# v1.net
KiCad netlist of a schematic drawn in EAGLE
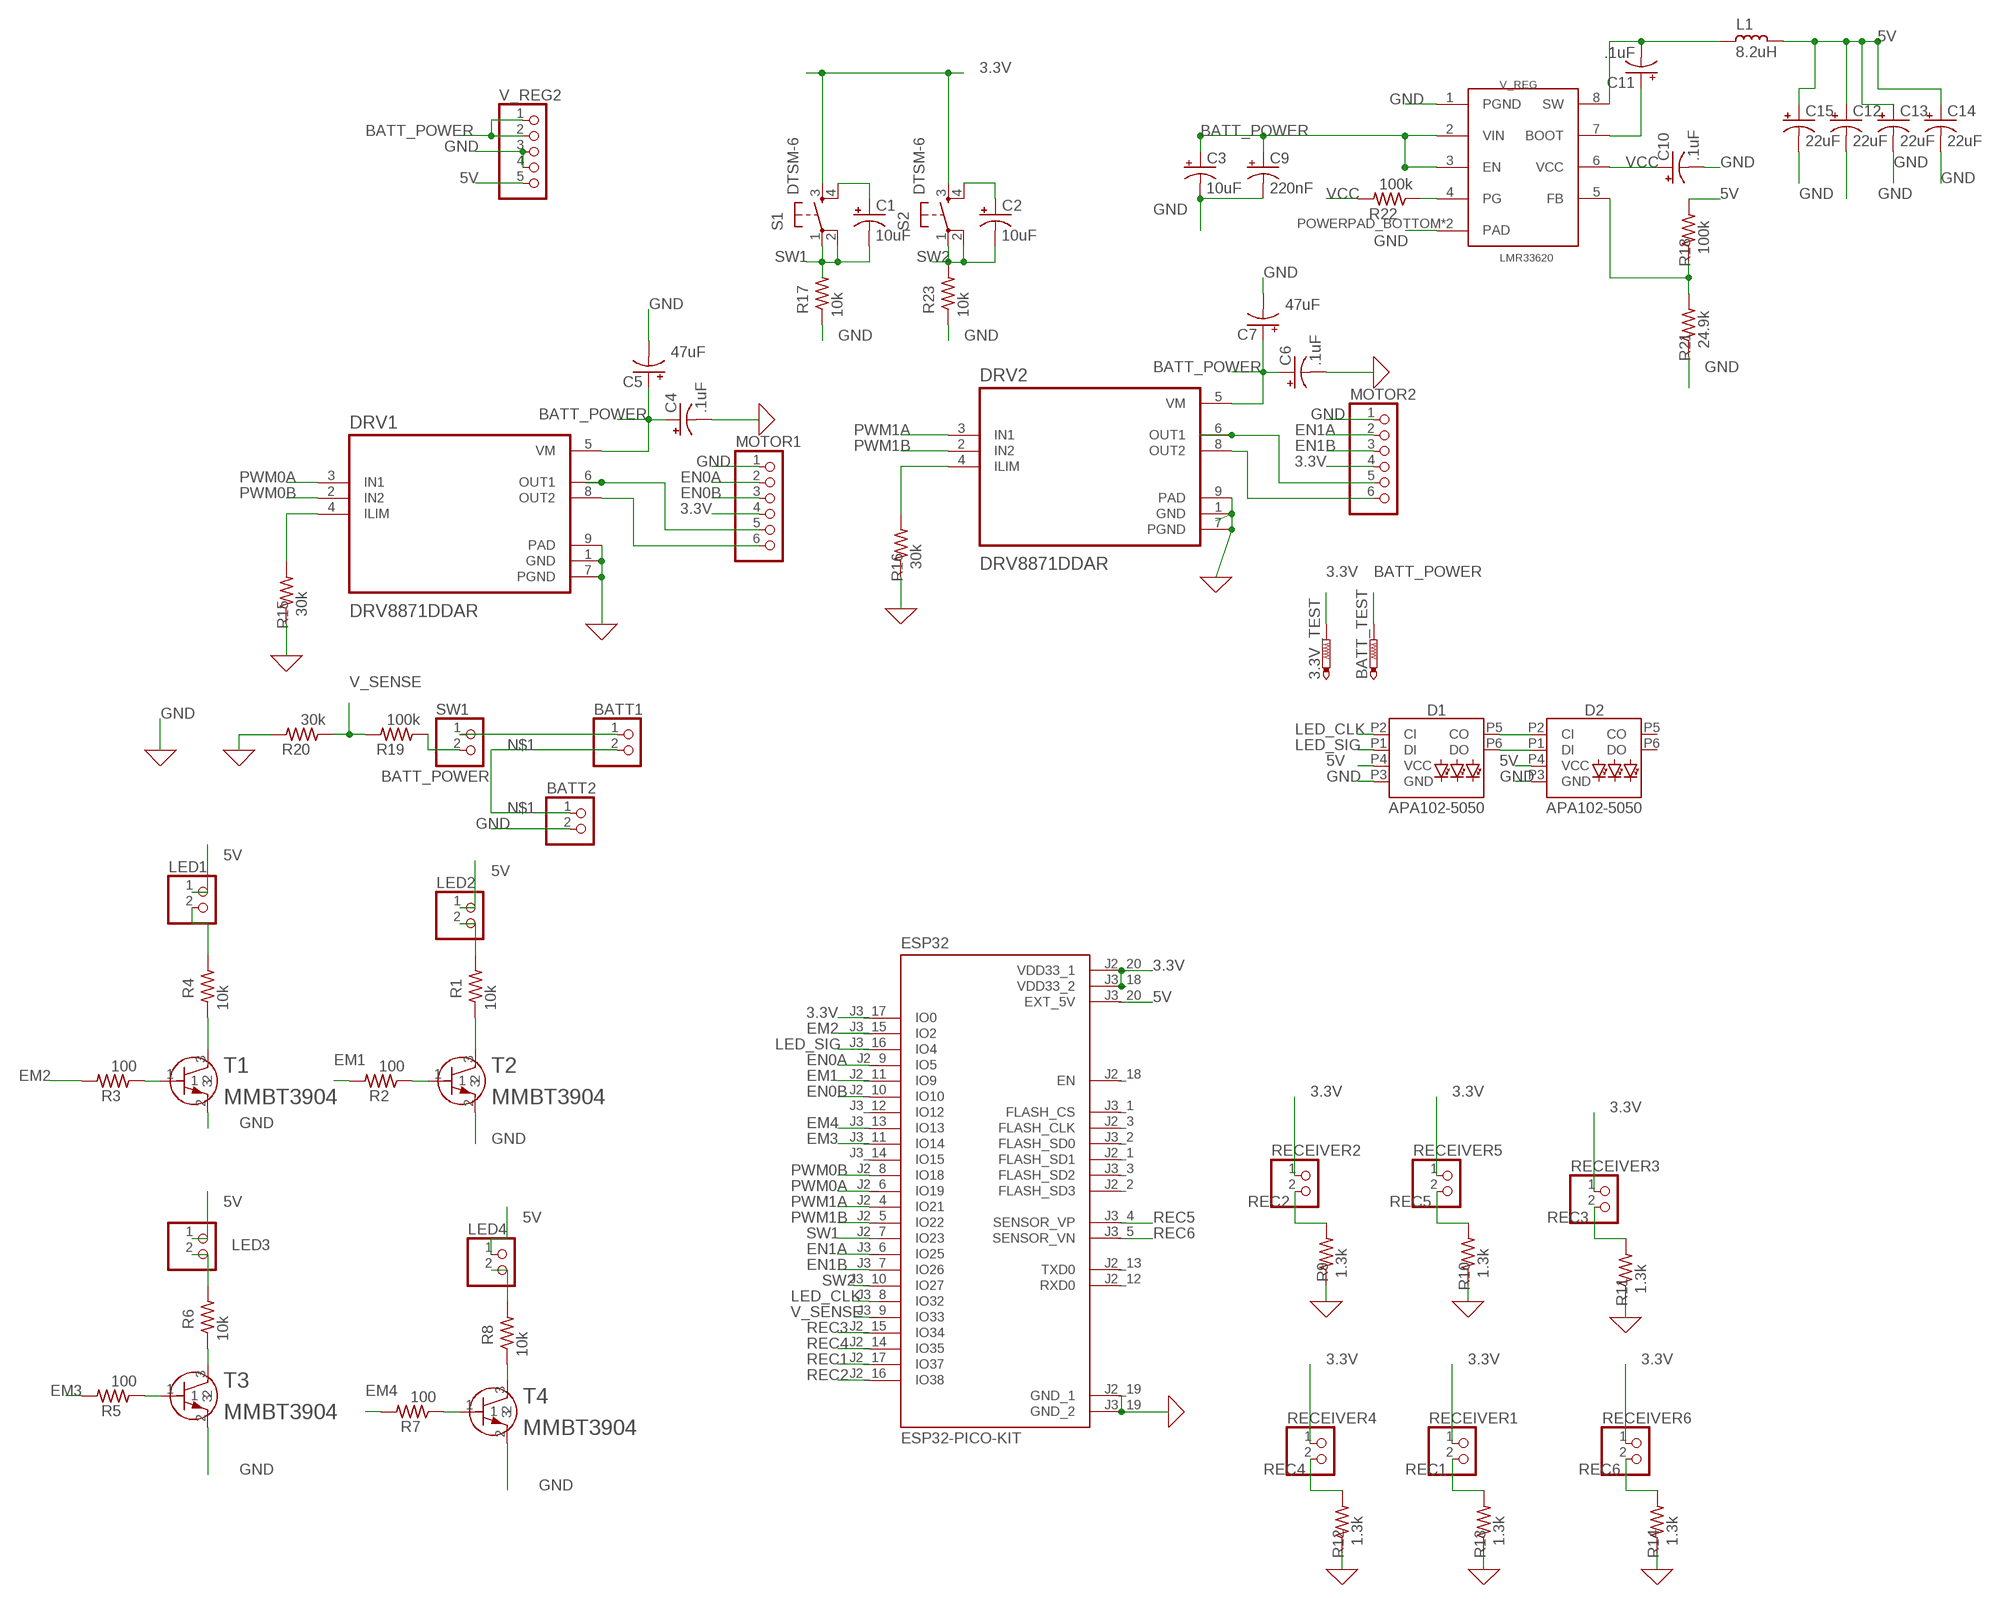
[diagram p0: schematic, sheet 1]

(export (version "E")
  (design (tool "Eeschema 10.0.6"))
  (components
    (comp (ref "3.3V_TEST")
      (value "PTR1B1,27")
      (footprint "eagle-import:B1,27")
      (libsource (lib "eagle-import") (part "PTR1B1,27"))
    )
    (comp (ref "BATT1")
      (value "PINHD-1X2")
      (footprint "eagle-import:1X02")
      (libsource (lib "eagle-import") (part "PINHD-1X2"))
    )
    (comp (ref "BATT2")
      (value "PINHD-1X2")
      (footprint "eagle-import:1X02")
      (libsource (lib "eagle-import") (part "PINHD-1X2"))
    )
    (comp (ref "BATT_TEST")
      (value "PTR1B1,27")
      (footprint "eagle-import:B1,27")
      (libsource (lib "eagle-import") (part "PTR1B1,27"))
    )
    (comp (ref "C1")
      (value "10uF")
      (footprint "eagle-import:A_3216-18R")
      (libsource (lib "eagle-import") (part "CPOL-USA/3216-18R"))
    )
    (comp (ref "C2")
      (value "10uF")
      (footprint "eagle-import:A_3216-18R")
      (libsource (lib "eagle-import") (part "CPOL-USA/3216-18R"))
    )
    (comp (ref "C3")
      (value "10uF")
      (footprint "eagle-import:A_3216-18R")
      (libsource (lib "eagle-import") (part "CPOL-USA/3216-18R"))
    )
    (comp (ref "C4")
      (value ".1uF")
      (footprint "eagle-import:A_3216-18R")
      (libsource (lib "eagle-import") (part "CPOL-USA/3216-18R"))
    )
    (comp (ref "C5")
      (value "47uF")
      (footprint "eagle-import:150CLZ-0810")
      (libsource (lib "eagle-import") (part "CPOL-US150CLZ-0810"))
    )
    (comp (ref "C6")
      (value ".1uF")
      (footprint "eagle-import:A_3216-18R")
      (libsource (lib "eagle-import") (part "CPOL-USA/3216-18R"))
    )
    (comp (ref "C7")
      (value "47uF")
      (footprint "eagle-import:150CLZ-0810")
      (libsource (lib "eagle-import") (part "CPOL-US150CLZ-0810"))
    )
    (comp (ref "C9")
      (value "220nF")
      (footprint "eagle-import:A_3216-18R")
      (libsource (lib "eagle-import") (part "CPOL-USA/3216-18R"))
    )
    (comp (ref "C10")
      (value ".1uF")
      (footprint "eagle-import:A_3216-18R")
      (libsource (lib "eagle-import") (part "CPOL-USA/3216-18R"))
    )
    (comp (ref "C11")
      (value ".1uF")
      (footprint "eagle-import:A_3216-18R")
      (libsource (lib "eagle-import") (part "CPOL-USA/3216-18R"))
    )
    (comp (ref "C12")
      (value "22uF")
      (footprint "eagle-import:A_3216-18R")
      (libsource (lib "eagle-import") (part "CPOL-USA/3216-18R"))
    )
    (comp (ref "C13")
      (value "22uF")
      (footprint "eagle-import:A_3216-18R")
      (libsource (lib "eagle-import") (part "CPOL-USA/3216-18R"))
    )
    (comp (ref "C14")
      (value "22uF")
      (footprint "eagle-import:A_3216-18R")
      (libsource (lib "eagle-import") (part "CPOL-USA/3216-18R"))
    )
    (comp (ref "C15")
      (value "22uF")
      (footprint "eagle-import:A_3216-18R")
      (libsource (lib "eagle-import") (part "CPOL-USA/3216-18R"))
    )
    (comp (ref "D1")
      (value "APA102-5050")
      (footprint "eagle-import:APA102-5050")
      (libsource (lib "eagle-import") (part "APA102-5050"))
    )
    (comp (ref "D2")
      (value "APA102-5050")
      (footprint "eagle-import:APA102-5050")
      (libsource (lib "eagle-import") (part "APA102-5050"))
    )
    (comp (ref "DRV1")
      (value "DRV8871DDAR")
      (footprint "eagle-import:SOIC127P600X170-8N")
      (fields (field (name "DIGI-KEY_PART_NUMBER") "296-43024-1-ND") (field (name "MF") "Texas Instruments"))
      (libsource (lib "eagle-import") (part "DRV8871DDAR"))
    )
    (comp (ref "DRV2")
      (value "DRV8871DDAR")
      (footprint "eagle-import:SOIC127P600X170-8N")
      (fields (field (name "DIGI-KEY_PART_NUMBER") "296-43024-1-ND") (field (name "MF") "Texas Instruments"))
      (libsource (lib "eagle-import") (part "DRV8871DDAR"))
    )
    (comp (ref "ESP32")
      (value "ESP32-PICO-KIT")
      (footprint "eagle-import:XCVR_ESP32-PICO-KIT")
      (fields (field (name "MF") "Espressif Systems"))
      (libsource (lib "eagle-import") (part "ESP32-PICO-KIT"))
    )
    (comp (ref "L1")
      (value "8.2uH")
      (footprint "eagle-import:PM1812")
      (libsource (lib "eagle-import") (part "L_PM1812"))
    )
    (comp (ref "LED1")
      (value "PINHD-1X2")
      (footprint "eagle-import:1X02")
      (libsource (lib "eagle-import") (part "PINHD-1X2"))
    )
    (comp (ref "LED2")
      (value "PINHD-1X2")
      (footprint "eagle-import:1X02")
      (libsource (lib "eagle-import") (part "PINHD-1X2"))
    )
    (comp (ref "LED3")
      (value "PINHD-1X2")
      (footprint "eagle-import:1X02")
      (libsource (lib "eagle-import") (part "PINHD-1X2"))
    )
    (comp (ref "LED4")
      (value "PINHD-1X2")
      (footprint "eagle-import:1X02")
      (libsource (lib "eagle-import") (part "PINHD-1X2"))
    )
    (comp (ref "MOTOR1")
      (value "PINHD-1X6")
      (footprint "eagle-import:1X06")
      (libsource (lib "eagle-import") (part "PINHD-1X6"))
    )
    (comp (ref "MOTOR2")
      (value "PINHD-1X6")
      (footprint "eagle-import:1X06")
      (libsource (lib "eagle-import") (part "PINHD-1X6"))
    )
    (comp (ref "R1")
      (value "10k")
      (footprint "eagle-import:M1206")
      (libsource (lib "eagle-import") (part "R-US_M1206"))
    )
    (comp (ref "R2")
      (value "100")
      (footprint "eagle-import:M1206")
      (libsource (lib "eagle-import") (part "R-US_M1206"))
    )
    (comp (ref "R3")
      (value "100")
      (footprint "eagle-import:M1206")
      (libsource (lib "eagle-import") (part "R-US_M1206"))
    )
    (comp (ref "R4")
      (value "10k")
      (footprint "eagle-import:M1206")
      (libsource (lib "eagle-import") (part "R-US_M1206"))
    )
    (comp (ref "R5")
      (value "100")
      (footprint "eagle-import:M1206")
      (libsource (lib "eagle-import") (part "R-US_M1206"))
    )
    (comp (ref "R6")
      (value "10k")
      (footprint "eagle-import:M1206")
      (libsource (lib "eagle-import") (part "R-US_M1206"))
    )
    (comp (ref "R7")
      (value "100")
      (footprint "eagle-import:M1206")
      (libsource (lib "eagle-import") (part "R-US_M1206"))
    )
    (comp (ref "R8")
      (value "10k")
      (footprint "eagle-import:M1206")
      (libsource (lib "eagle-import") (part "R-US_M1206"))
    )
    (comp (ref "R9")
      (value "1.3k")
      (footprint "eagle-import:M1206")
      (libsource (lib "eagle-import") (part "R-US_M1206"))
    )
    (comp (ref "R10")
      (value "1.3k")
      (footprint "eagle-import:M1206")
      (libsource (lib "eagle-import") (part "R-US_M1206"))
    )
    (comp (ref "R11")
      (value "1.3k")
      (footprint "eagle-import:M1206")
      (libsource (lib "eagle-import") (part "R-US_M1206"))
    )
    (comp (ref "R12")
      (value "1.3k")
      (footprint "eagle-import:M1206")
      (libsource (lib "eagle-import") (part "R-US_M1206"))
    )
    (comp (ref "R13")
      (value "1.3k")
      (footprint "eagle-import:M1206")
      (libsource (lib "eagle-import") (part "R-US_M1206"))
    )
    (comp (ref "R14")
      (value "1.3k")
      (footprint "eagle-import:M1206")
      (libsource (lib "eagle-import") (part "R-US_M1206"))
    )
    (comp (ref "R15")
      (value "30k")
      (footprint "eagle-import:M1206")
      (libsource (lib "eagle-import") (part "R-US_M1206"))
    )
    (comp (ref "R16")
      (value "30k")
      (footprint "eagle-import:M1206")
      (libsource (lib "eagle-import") (part "R-US_M1206"))
    )
    (comp (ref "R17")
      (value "10k")
      (footprint "eagle-import:M1206")
      (libsource (lib "eagle-import") (part "R-US_M1206"))
    )
    (comp (ref "R18")
      (value "100k")
      (footprint "eagle-import:M1206")
      (libsource (lib "eagle-import") (part "R-US_M1206"))
    )
    (comp (ref "R19")
      (value "100k")
      (footprint "eagle-import:M1206")
      (libsource (lib "eagle-import") (part "R-US_M1206"))
    )
    (comp (ref "R20")
      (value "30k")
      (footprint "eagle-import:M1206")
      (libsource (lib "eagle-import") (part "R-US_M1206"))
    )
    (comp (ref "R21")
      (value "24.9k")
      (footprint "eagle-import:M1206")
      (libsource (lib "eagle-import") (part "R-US_M1206"))
    )
    (comp (ref "R22")
      (value "100k")
      (footprint "eagle-import:M1206")
      (libsource (lib "eagle-import") (part "R-US_M1206"))
    )
    (comp (ref "R23")
      (value "10k")
      (footprint "eagle-import:M1206")
      (libsource (lib "eagle-import") (part "R-US_M1206"))
    )
    (comp (ref "RECEIVER1")
      (value "PINHD-1X2")
      (footprint "eagle-import:1X02")
      (libsource (lib "eagle-import") (part "PINHD-1X2"))
    )
    (comp (ref "RECEIVER2")
      (value "PINHD-1X2")
      (footprint "eagle-import:1X02")
      (libsource (lib "eagle-import") (part "PINHD-1X2"))
    )
    (comp (ref "RECEIVER3")
      (value "PINHD-1X2")
      (footprint "eagle-import:1X02")
      (libsource (lib "eagle-import") (part "PINHD-1X2"))
    )
    (comp (ref "RECEIVER4")
      (value "PINHD-1X2")
      (footprint "eagle-import:1X02")
      (libsource (lib "eagle-import") (part "PINHD-1X2"))
    )
    (comp (ref "RECEIVER5")
      (value "PINHD-1X2")
      (footprint "eagle-import:1X02")
      (libsource (lib "eagle-import") (part "PINHD-1X2"))
    )
    (comp (ref "RECEIVER6")
      (value "PINHD-1X2")
      (footprint "eagle-import:1X02")
      (libsource (lib "eagle-import") (part "PINHD-1X2"))
    )
    (comp (ref "S1")
      (value "DTSM-6")
      (footprint "eagle-import:DTSM-6")
      (libsource (lib "eagle-import") (part "DTSM-6"))
    )
    (comp (ref "S2")
      (value "DTSM-6")
      (footprint "eagle-import:DTSM-6")
      (libsource (lib "eagle-import") (part "DTSM-6"))
    )
    (comp (ref "SW1")
      (value "PINHD-1X2")
      (footprint "eagle-import:1X02")
      (libsource (lib "eagle-import") (part "PINHD-1X2"))
    )
    (comp (ref "T1")
      (value "MMBT3904")
      (footprint "eagle-import:SOT23")
      (libsource (lib "eagle-import") (part "MMBT3904"))
    )
    (comp (ref "T2")
      (value "MMBT3904")
      (footprint "eagle-import:SOT23")
      (libsource (lib "eagle-import") (part "MMBT3904"))
    )
    (comp (ref "T3")
      (value "MMBT3904")
      (footprint "eagle-import:SOT23")
      (libsource (lib "eagle-import") (part "MMBT3904"))
    )
    (comp (ref "T4")
      (value "MMBT3904")
      (footprint "eagle-import:SOT23")
      (libsource (lib "eagle-import") (part "MMBT3904"))
    )
    (comp (ref "V_REG")
      (value "LMR33620")
      (footprint "eagle-import:SO-8_POWERPAD")
      (libsource (lib "eagle-import") (part "LMR33620"))
    )
    (comp (ref "V_REG2")
      (value "PINHD-1X5")
      (footprint "eagle-import:1X05")
      (libsource (lib "eagle-import") (part "PINHD-1X5"))
    )
  )
  (nets
    (net (code "1") (name "/3.3V") (class "Default")
      (node (ref "3.3V_TEST") (pin "TP") (pinfunction "TP_TP") (pintype "input"))
      (node (ref "ESP32") (pin "J2_20") (pinfunction "VDD33_1_J2_20") (pintype "power_in"))
      (node (ref "ESP32") (pin "J3_17") (pinfunction "IO0_J3_17") (pintype "bidirectional"))
      (node (ref "ESP32") (pin "J3_18") (pinfunction "VDD33_2_J3_18") (pintype "power_in"))
      (node (ref "MOTOR1") (pin "4") (pinfunction "4_4") (pintype "passive"))
      (node (ref "MOTOR2") (pin "4") (pinfunction "4_4") (pintype "passive"))
      (node (ref "RECEIVER1") (pin "1") (pinfunction "1_1") (pintype "passive"))
      (node (ref "RECEIVER2") (pin "1") (pinfunction "1_1") (pintype "passive"))
      (node (ref "RECEIVER3") (pin "1") (pinfunction "1_1") (pintype "passive"))
      (node (ref "RECEIVER4") (pin "1") (pinfunction "1_1") (pintype "passive"))
      (node (ref "RECEIVER5") (pin "1") (pinfunction "1_1") (pintype "passive"))
      (node (ref "RECEIVER6") (pin "1") (pinfunction "1_1") (pintype "passive"))
      (node (ref "S1") (pin "3") (pinfunction "3_3") (pintype "passive"))
      (node (ref "S2") (pin "3") (pinfunction "3_3") (pintype "passive"))
    )
    (net (code "2") (name "/5V") (class "Default")
      (node (ref "C12") (pin "+") (pinfunction "+_+") (pintype "passive"))
      (node (ref "C13") (pin "+") (pinfunction "+_+") (pintype "passive"))
      (node (ref "C14") (pin "+") (pinfunction "+_+") (pintype "passive"))
      (node (ref "C15") (pin "+") (pinfunction "+_+") (pintype "passive"))
      (node (ref "D1") (pin "P4") (pinfunction "VCC_P4") (pintype "bidirectional"))
      (node (ref "D2") (pin "P4") (pinfunction "VCC_P4") (pintype "bidirectional"))
      (node (ref "ESP32") (pin "J3_20") (pinfunction "EXT_5V_J3_20") (pintype "power_in"))
      (node (ref "L1") (pin "1") (pinfunction "1_1") (pintype "passive"))
      (node (ref "LED1") (pin "1") (pinfunction "1_1") (pintype "passive"))
      (node (ref "LED2") (pin "1") (pinfunction "1_1") (pintype "passive"))
      (node (ref "LED3") (pin "1") (pinfunction "1_1") (pintype "passive"))
      (node (ref "LED4") (pin "1") (pinfunction "1_1") (pintype "passive"))
      (node (ref "R18") (pin "2") (pinfunction "2_2") (pintype "passive"))
      (node (ref "V_REG2") (pin "5") (pinfunction "5_5") (pintype "passive"))
    )
    (net (code "3") (name "/BATT_POWER") (class "Default")
      (node (ref "BATT_TEST") (pin "TP") (pinfunction "TP_TP") (pintype "input"))
      (node (ref "C3") (pin "+") (pinfunction "+_+") (pintype "passive"))
      (node (ref "C4") (pin "+") (pinfunction "+_+") (pintype "passive"))
      (node (ref "C5") (pin "+") (pinfunction "+_+") (pintype "passive"))
      (node (ref "C6") (pin "+") (pinfunction "+_+") (pintype "passive"))
      (node (ref "C7") (pin "+") (pinfunction "+_+") (pintype "passive"))
      (node (ref "C9") (pin "+") (pinfunction "+_+") (pintype "passive"))
      (node (ref "DRV1") (pin "5") (pinfunction "VM_5") (pintype "power_in"))
      (node (ref "DRV2") (pin "5") (pinfunction "VM_5") (pintype "power_in"))
      (node (ref "R19") (pin "1") (pinfunction "1_1") (pintype "passive"))
      (node (ref "SW1") (pin "2") (pinfunction "2_2") (pintype "passive"))
      (node (ref "V_REG") (pin "2") (pinfunction "VIN_2") (pintype "bidirectional"))
      (node (ref "V_REG") (pin "3") (pinfunction "EN_3") (pintype "bidirectional"))
      (node (ref "V_REG2") (pin "1") (pinfunction "1_1") (pintype "passive"))
      (node (ref "V_REG2") (pin "2") (pinfunction "2_2") (pintype "passive"))
    )
    (net (code "4") (name "/EM1") (class "Default")
      (node (ref "ESP32") (pin "J2_11") (pinfunction "IO9_J2_11") (pintype "bidirectional"))
      (node (ref "R2") (pin "2") (pinfunction "2_2") (pintype "passive"))
    )
    (net (code "5") (name "/EM2") (class "Default")
      (node (ref "ESP32") (pin "J3_15") (pinfunction "IO2_J3_15") (pintype "bidirectional"))
      (node (ref "R3") (pin "2") (pinfunction "2_2") (pintype "passive"))
    )
    (net (code "6") (name "/EM3") (class "Default")
      (node (ref "ESP32") (pin "J3_11") (pinfunction "IO14_J3_11") (pintype "bidirectional"))
      (node (ref "R5") (pin "2") (pinfunction "2_2") (pintype "passive"))
    )
    (net (code "7") (name "/EM4") (class "Default")
      (node (ref "ESP32") (pin "J3_13") (pinfunction "IO13_J3_13") (pintype "bidirectional"))
      (node (ref "R7") (pin "2") (pinfunction "2_2") (pintype "passive"))
    )
    (net (code "8") (name "/EN0A") (class "Default")
      (node (ref "ESP32") (pin "J2_9") (pinfunction "IO5_J2_9") (pintype "bidirectional"))
      (node (ref "MOTOR1") (pin "2") (pinfunction "2_2") (pintype "passive"))
    )
    (net (code "9") (name "/EN0B") (class "Default")
      (node (ref "ESP32") (pin "J2_10") (pinfunction "IO10_J2_10") (pintype "bidirectional"))
      (node (ref "MOTOR1") (pin "3") (pinfunction "3_3") (pintype "passive"))
    )
    (net (code "10") (name "/EN1A") (class "Default")
      (node (ref "ESP32") (pin "J3_6") (pinfunction "IO25_J3_6") (pintype "bidirectional"))
      (node (ref "MOTOR2") (pin "2") (pinfunction "2_2") (pintype "passive"))
    )
    (net (code "11") (name "/EN1B") (class "Default")
      (node (ref "ESP32") (pin "J3_7") (pinfunction "IO26_J3_7") (pintype "bidirectional"))
      (node (ref "MOTOR2") (pin "3") (pinfunction "3_3") (pintype "passive"))
    )
    (net (code "12") (name "/LED_CLK") (class "Default")
      (node (ref "D1") (pin "P2") (pinfunction "CI_P2") (pintype "bidirectional"))
      (node (ref "ESP32") (pin "J3_8") (pinfunction "IO32_J3_8") (pintype "bidirectional"))
    )
    (net (code "13") (name "/LED_SIG") (class "Default")
      (node (ref "D1") (pin "P1") (pinfunction "DI_P1") (pintype "bidirectional"))
      (node (ref "ESP32") (pin "J3_16") (pinfunction "IO4_J3_16") (pintype "bidirectional"))
    )
    (net (code "14") (name "/N$1") (class "Default")
      (node (ref "BATT1") (pin "2") (pinfunction "2_2") (pintype "passive"))
      (node (ref "BATT2") (pin "1") (pinfunction "1_1") (pintype "passive"))
    )
    (net (code "15") (name "/PWM0A") (class "Default")
      (node (ref "DRV1") (pin "3") (pinfunction "IN1_3") (pintype "input"))
      (node (ref "ESP32") (pin "J2_6") (pinfunction "IO19_J2_6") (pintype "bidirectional"))
    )
    (net (code "16") (name "/PWM0B") (class "Default")
      (node (ref "DRV1") (pin "2") (pinfunction "IN2_2") (pintype "input"))
      (node (ref "ESP32") (pin "J2_8") (pinfunction "IO18_J2_8") (pintype "bidirectional"))
    )
    (net (code "17") (name "/PWM1A") (class "Default")
      (node (ref "DRV2") (pin "3") (pinfunction "IN1_3") (pintype "input"))
      (node (ref "ESP32") (pin "J2_4") (pinfunction "IO21_J2_4") (pintype "bidirectional"))
    )
    (net (code "18") (name "/PWM1B") (class "Default")
      (node (ref "DRV2") (pin "2") (pinfunction "IN2_2") (pintype "input"))
      (node (ref "ESP32") (pin "J2_5") (pinfunction "IO22_J2_5") (pintype "bidirectional"))
    )
    (net (code "19") (name "/REC1") (class "Default")
      (node (ref "ESP32") (pin "J2_17") (pinfunction "IO37_J2_17") (pintype "input"))
      (node (ref "R13") (pin "2") (pinfunction "2_2") (pintype "passive"))
      (node (ref "RECEIVER1") (pin "2") (pinfunction "2_2") (pintype "passive"))
    )
    (net (code "20") (name "/REC2") (class "Default")
      (node (ref "ESP32") (pin "J2_16") (pinfunction "IO38_J2_16") (pintype "input"))
      (node (ref "R9") (pin "2") (pinfunction "2_2") (pintype "passive"))
      (node (ref "RECEIVER2") (pin "2") (pinfunction "2_2") (pintype "passive"))
    )
    (net (code "21") (name "/REC3") (class "Default")
      (node (ref "ESP32") (pin "J2_15") (pinfunction "IO34_J2_15") (pintype "input"))
      (node (ref "R11") (pin "2") (pinfunction "2_2") (pintype "passive"))
      (node (ref "RECEIVER3") (pin "2") (pinfunction "2_2") (pintype "passive"))
    )
    (net (code "22") (name "/REC4") (class "Default")
      (node (ref "ESP32") (pin "J2_14") (pinfunction "IO35_J2_14") (pintype "input"))
      (node (ref "R12") (pin "2") (pinfunction "2_2") (pintype "passive"))
      (node (ref "RECEIVER4") (pin "2") (pinfunction "2_2") (pintype "passive"))
    )
    (net (code "23") (name "/REC5") (class "Default")
      (node (ref "ESP32") (pin "J3_4") (pinfunction "SENSOR_VP_J3_4") (pintype "input"))
      (node (ref "R10") (pin "2") (pinfunction "2_2") (pintype "passive"))
      (node (ref "RECEIVER5") (pin "2") (pinfunction "2_2") (pintype "passive"))
    )
    (net (code "24") (name "/REC6") (class "Default")
      (node (ref "ESP32") (pin "J3_5") (pinfunction "SENSOR_VN_J3_5") (pintype "input"))
      (node (ref "R14") (pin "2") (pinfunction "2_2") (pintype "passive"))
      (node (ref "RECEIVER6") (pin "2") (pinfunction "2_2") (pintype "passive"))
    )
    (net (code "25") (name "/SW1") (class "Default")
      (node (ref "C1") (pin "-") (pinfunction "-_-") (pintype "passive"))
      (node (ref "ESP32") (pin "J2_7") (pinfunction "IO23_J2_7") (pintype "bidirectional"))
      (node (ref "R17") (pin "2") (pinfunction "2_2") (pintype "passive"))
      (node (ref "S1") (pin "1") (pinfunction "1_1") (pintype "passive"))
      (node (ref "S1") (pin "2") (pinfunction "2_2") (pintype "passive"))
    )
    (net (code "26") (name "/SW2") (class "Default")
      (node (ref "C2") (pin "-") (pinfunction "-_-") (pintype "passive"))
      (node (ref "ESP32") (pin "J3_10") (pinfunction "IO27_J3_10") (pintype "bidirectional"))
      (node (ref "R23") (pin "2") (pinfunction "2_2") (pintype "passive"))
      (node (ref "S2") (pin "1") (pinfunction "1_1") (pintype "passive"))
      (node (ref "S2") (pin "2") (pinfunction "2_2") (pintype "passive"))
    )
    (net (code "27") (name "/VCC") (class "Default")
      (node (ref "C10") (pin "+") (pinfunction "+_+") (pintype "passive"))
      (node (ref "R22") (pin "2") (pinfunction "2_2") (pintype "passive"))
      (node (ref "V_REG") (pin "6") (pinfunction "VCC_6") (pintype "bidirectional"))
    )
    (net (code "28") (name "/V_SENSE") (class "Default")
      (node (ref "ESP32") (pin "J3_9") (pinfunction "IO33_J3_9") (pintype "bidirectional"))
      (node (ref "R19") (pin "2") (pinfunction "2_2") (pintype "passive"))
      (node (ref "R20") (pin "1") (pinfunction "1_1") (pintype "passive"))
    )
    (net (code "29") (name "GND") (class "Default")
      (node (ref "BATT2") (pin "2") (pinfunction "2_2") (pintype "passive"))
      (node (ref "C10") (pin "-") (pinfunction "-_-") (pintype "passive"))
      (node (ref "C12") (pin "-") (pinfunction "-_-") (pintype "passive"))
      (node (ref "C13") (pin "-") (pinfunction "-_-") (pintype "passive"))
      (node (ref "C14") (pin "-") (pinfunction "-_-") (pintype "passive"))
      (node (ref "C15") (pin "-") (pinfunction "-_-") (pintype "passive"))
      (node (ref "C3") (pin "-") (pinfunction "-_-") (pintype "passive"))
      (node (ref "C4") (pin "-") (pinfunction "-_-") (pintype "passive"))
      (node (ref "C5") (pin "-") (pinfunction "-_-") (pintype "passive"))
      (node (ref "C6") (pin "-") (pinfunction "-_-") (pintype "passive"))
      (node (ref "C7") (pin "-") (pinfunction "-_-") (pintype "passive"))
      (node (ref "C9") (pin "-") (pinfunction "-_-") (pintype "passive"))
      (node (ref "D1") (pin "P3") (pinfunction "GND_P3") (pintype "bidirectional"))
      (node (ref "D2") (pin "P3") (pinfunction "GND_P3") (pintype "bidirectional"))
      (node (ref "DRV1") (pin "1") (pinfunction "GND_1") (pintype "power_in"))
      (node (ref "DRV1") (pin "7") (pinfunction "PGND_7") (pintype "power_in"))
      (node (ref "DRV1") (pin "9") (pinfunction "PAD_9") (pintype "power_in"))
      (node (ref "DRV2") (pin "1") (pinfunction "GND_1") (pintype "power_in"))
      (node (ref "DRV2") (pin "7") (pinfunction "PGND_7") (pintype "power_in"))
      (node (ref "DRV2") (pin "9") (pinfunction "PAD_9") (pintype "power_in"))
      (node (ref "ESP32") (pin "J2_19") (pinfunction "GND_1_J2_19") (pintype "power_in"))
      (node (ref "ESP32") (pin "J3_19") (pinfunction "GND_2_J3_19") (pintype "power_in"))
      (node (ref "MOTOR1") (pin "1") (pinfunction "1_1") (pintype "passive"))
      (node (ref "MOTOR2") (pin "1") (pinfunction "1_1") (pintype "passive"))
      (node (ref "R10") (pin "1") (pinfunction "1_1") (pintype "passive"))
      (node (ref "R11") (pin "1") (pinfunction "1_1") (pintype "passive"))
      (node (ref "R12") (pin "1") (pinfunction "1_1") (pintype "passive"))
      (node (ref "R13") (pin "1") (pinfunction "1_1") (pintype "passive"))
      (node (ref "R14") (pin "1") (pinfunction "1_1") (pintype "passive"))
      (node (ref "R15") (pin "1") (pinfunction "1_1") (pintype "passive"))
      (node (ref "R16") (pin "1") (pinfunction "1_1") (pintype "passive"))
      (node (ref "R17") (pin "1") (pinfunction "1_1") (pintype "passive"))
      (node (ref "R20") (pin "2") (pinfunction "2_2") (pintype "passive"))
      (node (ref "R21") (pin "1") (pinfunction "1_1") (pintype "passive"))
      (node (ref "R23") (pin "1") (pinfunction "1_1") (pintype "passive"))
      (node (ref "R9") (pin "1") (pinfunction "1_1") (pintype "passive"))
      (node (ref "T1") (pin "2") (pinfunction "2_2") (pintype "passive"))
      (node (ref "T2") (pin "2") (pinfunction "2_2") (pintype "passive"))
      (node (ref "T3") (pin "2") (pinfunction "2_2") (pintype "passive"))
      (node (ref "T4") (pin "2") (pinfunction "2_2") (pintype "passive"))
      (node (ref "V_REG") (pin "1") (pinfunction "PGND_1") (pintype "bidirectional"))
      (node (ref "V_REG") (pin "POWERPAD_BOTTOM") (pinfunction "PAD_POWERPAD_BOTTOM") (pintype "bidirectional"))
      (node (ref "V_REG") (pin "POWERPAD_TOP") (pinfunction "PAD_POWERPAD_TOP") (pintype "bidirectional"))
      (node (ref "V_REG2") (pin "3") (pinfunction "3_3") (pintype "passive"))
      (node (ref "V_REG2") (pin "4") (pinfunction "4_4") (pintype "passive"))
    )
    (net (code "30") (name "Net-(BATT1-Pad1)") (class "Default")
      (node (ref "BATT1") (pin "1") (pinfunction "1_1") (pintype "passive"))
      (node (ref "SW1") (pin "1") (pinfunction "1_1") (pintype "passive"))
    )
    (net (code "31") (name "Net-(C1-Pad+)") (class "Default")
      (node (ref "C1") (pin "+") (pinfunction "+_+") (pintype "passive"))
      (node (ref "S1") (pin "4") (pinfunction "4_4") (pintype "passive"))
    )
    (net (code "32") (name "Net-(C2-Pad+)") (class "Default")
      (node (ref "C2") (pin "+") (pinfunction "+_+") (pintype "passive"))
      (node (ref "S2") (pin "4") (pinfunction "4_4") (pintype "passive"))
    )
    (net (code "33") (name "Net-(D1-CO)") (class "Default")
      (node (ref "D1") (pin "P5") (pinfunction "CO_P5") (pintype "bidirectional"))
      (node (ref "D2") (pin "P2") (pinfunction "CI_P2") (pintype "bidirectional"))
    )
    (net (code "34") (name "Net-(D1-DO)") (class "Default")
      (node (ref "D1") (pin "P6") (pinfunction "DO_P6") (pintype "bidirectional"))
      (node (ref "D2") (pin "P1") (pinfunction "DI_P1") (pintype "bidirectional"))
    )
    (net (code "35") (name "Net-(DRV1-ILIM)") (class "Default")
      (node (ref "DRV1") (pin "4") (pinfunction "ILIM_4") (pintype "input"))
      (node (ref "R15") (pin "2") (pinfunction "2_2") (pintype "passive"))
    )
    (net (code "36") (name "Net-(DRV1-OUT1)") (class "Default")
      (node (ref "DRV1") (pin "6") (pinfunction "OUT1_6") (pintype "output"))
      (node (ref "MOTOR1") (pin "5") (pinfunction "5_5") (pintype "passive"))
    )
    (net (code "37") (name "Net-(DRV1-OUT2)") (class "Default")
      (node (ref "DRV1") (pin "8") (pinfunction "OUT2_8") (pintype "output"))
      (node (ref "MOTOR1") (pin "6") (pinfunction "6_6") (pintype "passive"))
    )
    (net (code "38") (name "Net-(DRV2-ILIM)") (class "Default")
      (node (ref "DRV2") (pin "4") (pinfunction "ILIM_4") (pintype "input"))
      (node (ref "R16") (pin "2") (pinfunction "2_2") (pintype "passive"))
    )
    (net (code "39") (name "Net-(DRV2-OUT1)") (class "Default")
      (node (ref "DRV2") (pin "6") (pinfunction "OUT1_6") (pintype "output"))
      (node (ref "MOTOR2") (pin "5") (pinfunction "5_5") (pintype "passive"))
    )
    (net (code "40") (name "Net-(DRV2-OUT2)") (class "Default")
      (node (ref "DRV2") (pin "8") (pinfunction "OUT2_8") (pintype "output"))
      (node (ref "MOTOR2") (pin "6") (pinfunction "6_6") (pintype "passive"))
    )
    (net (code "41") (name "Net-(LED1-Pad2)") (class "Default")
      (node (ref "LED1") (pin "2") (pinfunction "2_2") (pintype "passive"))
      (node (ref "R4") (pin "2") (pinfunction "2_2") (pintype "passive"))
    )
    (net (code "42") (name "Net-(LED2-Pad2)") (class "Default")
      (node (ref "LED2") (pin "2") (pinfunction "2_2") (pintype "passive"))
      (node (ref "R1") (pin "2") (pinfunction "2_2") (pintype "passive"))
    )
    (net (code "43") (name "Net-(LED3-Pad2)") (class "Default")
      (node (ref "LED3") (pin "2") (pinfunction "2_2") (pintype "passive"))
      (node (ref "R6") (pin "2") (pinfunction "2_2") (pintype "passive"))
    )
    (net (code "44") (name "Net-(LED4-Pad2)") (class "Default")
      (node (ref "LED4") (pin "2") (pinfunction "2_2") (pintype "passive"))
      (node (ref "R8") (pin "2") (pinfunction "2_2") (pintype "passive"))
    )
    (net (code "45") (name "Net-(R1-Pad1)") (class "Default")
      (node (ref "R1") (pin "1") (pinfunction "1_1") (pintype "passive"))
      (node (ref "T2") (pin "3") (pinfunction "3_3") (pintype "passive"))
    )
    (net (code "46") (name "Net-(R2-Pad1)") (class "Default")
      (node (ref "R2") (pin "1") (pinfunction "1_1") (pintype "passive"))
      (node (ref "T2") (pin "1") (pinfunction "1_1") (pintype "passive"))
    )
    (net (code "47") (name "Net-(R3-Pad1)") (class "Default")
      (node (ref "R3") (pin "1") (pinfunction "1_1") (pintype "passive"))
      (node (ref "T1") (pin "1") (pinfunction "1_1") (pintype "passive"))
    )
    (net (code "48") (name "Net-(R4-Pad1)") (class "Default")
      (node (ref "R4") (pin "1") (pinfunction "1_1") (pintype "passive"))
      (node (ref "T1") (pin "3") (pinfunction "3_3") (pintype "passive"))
    )
    (net (code "49") (name "Net-(R5-Pad1)") (class "Default")
      (node (ref "R5") (pin "1") (pinfunction "1_1") (pintype "passive"))
      (node (ref "T3") (pin "1") (pinfunction "1_1") (pintype "passive"))
    )
    (net (code "50") (name "Net-(R6-Pad1)") (class "Default")
      (node (ref "R6") (pin "1") (pinfunction "1_1") (pintype "passive"))
      (node (ref "T3") (pin "3") (pinfunction "3_3") (pintype "passive"))
    )
    (net (code "51") (name "Net-(R7-Pad1)") (class "Default")
      (node (ref "R7") (pin "1") (pinfunction "1_1") (pintype "passive"))
      (node (ref "T4") (pin "1") (pinfunction "1_1") (pintype "passive"))
    )
    (net (code "52") (name "Net-(R8-Pad1)") (class "Default")
      (node (ref "R8") (pin "1") (pinfunction "1_1") (pintype "passive"))
      (node (ref "T4") (pin "3") (pinfunction "3_3") (pintype "passive"))
    )
    (net (code "53") (name "Net-(V_REG-BOOT)") (class "Default")
      (node (ref "C11") (pin "+") (pinfunction "+_+") (pintype "passive"))
      (node (ref "V_REG") (pin "7") (pinfunction "BOOT_7") (pintype "bidirectional"))
    )
    (net (code "54") (name "Net-(V_REG-FB)") (class "Default")
      (node (ref "R18") (pin "1") (pinfunction "1_1") (pintype "passive"))
      (node (ref "R21") (pin "2") (pinfunction "2_2") (pintype "passive"))
      (node (ref "V_REG") (pin "5") (pinfunction "FB_5") (pintype "bidirectional"))
    )
    (net (code "55") (name "Net-(V_REG-PG)") (class "Default")
      (node (ref "R22") (pin "1") (pinfunction "1_1") (pintype "passive"))
      (node (ref "V_REG") (pin "4") (pinfunction "PG_4") (pintype "bidirectional"))
    )
    (net (code "56") (name "Net-(V_REG-SW)") (class "Default")
      (node (ref "C11") (pin "-") (pinfunction "-_-") (pintype "passive"))
      (node (ref "L1") (pin "2") (pinfunction "2_2") (pintype "passive"))
      (node (ref "V_REG") (pin "8") (pinfunction "SW_8") (pintype "bidirectional"))
    )
    (net (code "57") (name "unconnected-(D2-CO-PadP5)") (class "Default")
      (node (ref "D2") (pin "P5") (pinfunction "CO_P5") (pintype "bidirectional"))
    )
    (net (code "58") (name "unconnected-(D2-DO-PadP6)") (class "Default")
      (node (ref "D2") (pin "P6") (pinfunction "DO_P6") (pintype "bidirectional"))
    )
    (net (code "59") (name "unconnected-(ESP32-EN-PadJ2_18)") (class "Default")
      (node (ref "ESP32") (pin "J2_18") (pinfunction "EN_J2_18") (pintype "input"))
    )
    (net (code "60") (name "unconnected-(ESP32-FLASH_CLK-PadJ2_3)") (class "Default")
      (node (ref "ESP32") (pin "J2_3") (pinfunction "FLASH_CLK_J2_3") (pintype "bidirectional"))
    )
    (net (code "61") (name "unconnected-(ESP32-FLASH_CS-PadJ3_1)") (class "Default")
      (node (ref "ESP32") (pin "J3_1") (pinfunction "FLASH_CS_J3_1") (pintype "bidirectional"))
    )
    (net (code "62") (name "unconnected-(ESP32-FLASH_SD0-PadJ3_2)") (class "Default")
      (node (ref "ESP32") (pin "J3_2") (pinfunction "FLASH_SD0_J3_2") (pintype "bidirectional"))
    )
    (net (code "63") (name "unconnected-(ESP32-FLASH_SD1-PadJ2_1)") (class "Default")
      (node (ref "ESP32") (pin "J2_1") (pinfunction "FLASH_SD1_J2_1") (pintype "bidirectional"))
    )
    (net (code "64") (name "unconnected-(ESP32-FLASH_SD2-PadJ3_3)") (class "Default")
      (node (ref "ESP32") (pin "J3_3") (pinfunction "FLASH_SD2_J3_3") (pintype "bidirectional"))
    )
    (net (code "65") (name "unconnected-(ESP32-FLASH_SD3-PadJ2_2)") (class "Default")
      (node (ref "ESP32") (pin "J2_2") (pinfunction "FLASH_SD3_J2_2") (pintype "bidirectional"))
    )
    (net (code "66") (name "unconnected-(ESP32-IO12-PadJ3_12)") (class "Default")
      (node (ref "ESP32") (pin "J3_12") (pinfunction "IO12_J3_12") (pintype "bidirectional"))
    )
    (net (code "67") (name "unconnected-(ESP32-IO15-PadJ3_14)") (class "Default")
      (node (ref "ESP32") (pin "J3_14") (pinfunction "IO15_J3_14") (pintype "bidirectional"))
    )
    (net (code "68") (name "unconnected-(ESP32-RXD0-PadJ2_12)") (class "Default")
      (node (ref "ESP32") (pin "J2_12") (pinfunction "RXD0_J2_12") (pintype "bidirectional"))
    )
    (net (code "69") (name "unconnected-(ESP32-TXD0-PadJ2_13)") (class "Default")
      (node (ref "ESP32") (pin "J2_13") (pinfunction "TXD0_J2_13") (pintype "bidirectional"))
    )
  )
)
